# OmniMotor_MotorOnly.net
KiCad netlist of a schematic drawn in EAGLE
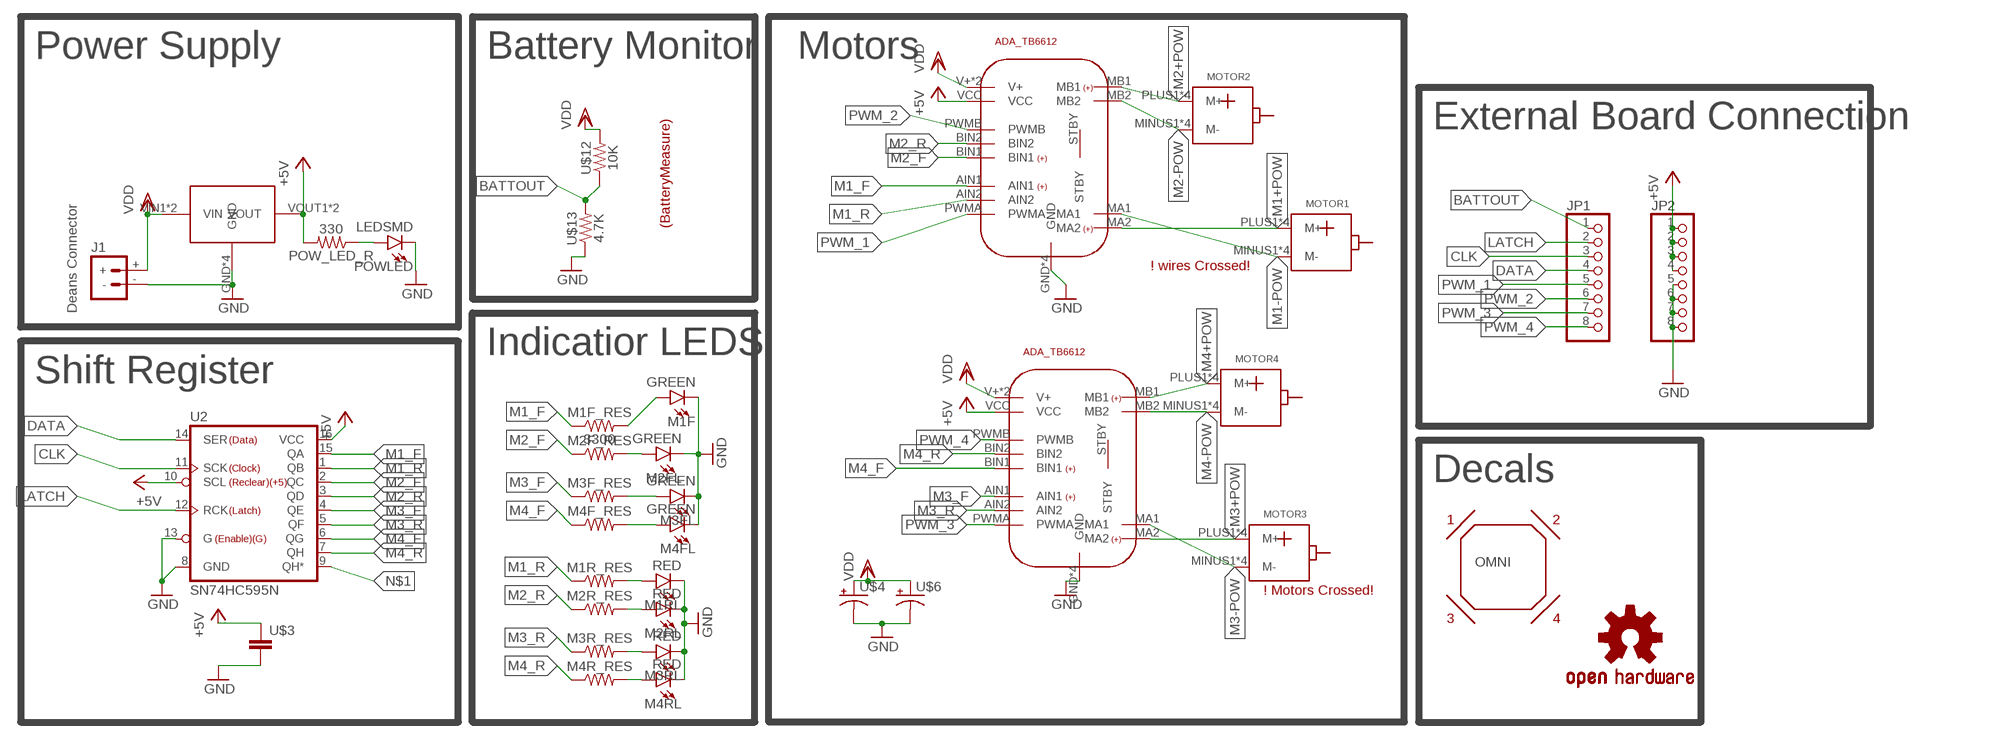
[diagram p0: schematic, sheet 1]

(export (version "E")
  (design (tool "Eeschema 10.0.6"))
  (components
    (comp (ref "J1")
      (value "BATTERY_CONN_DEANS")
      (footprint "eagle-import:DEANS")
      (libsource (lib "eagle-import") (part "BATTERY_CONN_DEANS"))
    )
    (comp (ref "JP1")
      (value "PINHD-1X8BIG")
      (footprint "eagle-import:1X08-BIG")
      (libsource (lib "eagle-import") (part "PINHD-1X8BIG"))
    )
    (comp (ref "JP2")
      (value "PINHD-1X8BIG")
      (footprint "eagle-import:1X08-BIG")
      (libsource (lib "eagle-import") (part "PINHD-1X8BIG"))
    )
    (comp (ref "LOGO1")
      (value "OSHW-LOGOL")
      (footprint "eagle-import:OSHW-LOGO-L")
      (libsource (lib "eagle-import") (part "OSHW-LOGOL"))
    )
    (comp (ref "M1F")
      (value "GREEN")
      (footprint "eagle-import:LED_SMD")
      (libsource (lib "eagle-import") (part "LEDSMD"))
    )
    (comp (ref "M1F_RES")
      (value "3300")
      (footprint "eagle-import:R1206")
      (libsource (lib "eagle-import") (part "RESISTORSMD"))
    )
    (comp (ref "M1RL")
      (value "RED")
      (footprint "eagle-import:LED_SMD")
      (libsource (lib "eagle-import") (part "LEDSMD"))
    )
    (comp (ref "M1R_RES")
      (value "RESISTORSMD")
      (footprint "eagle-import:R1206")
      (libsource (lib "eagle-import") (part "RESISTORSMD"))
    )
    (comp (ref "M2FL")
      (value "GREEN")
      (footprint "eagle-import:LED_SMD")
      (libsource (lib "eagle-import") (part "LEDSMD"))
    )
    (comp (ref "M2F_RES")
      (value "RESISTORSMD")
      (footprint "eagle-import:R1206")
      (libsource (lib "eagle-import") (part "RESISTORSMD"))
    )
    (comp (ref "M2RL")
      (value "RED")
      (footprint "eagle-import:LED_SMD")
      (libsource (lib "eagle-import") (part "LEDSMD"))
    )
    (comp (ref "M2R_RES")
      (value "RESISTORSMD")
      (footprint "eagle-import:R1206")
      (libsource (lib "eagle-import") (part "RESISTORSMD"))
    )
    (comp (ref "M3FL")
      (value "GREEN")
      (footprint "eagle-import:LED_SMD")
      (libsource (lib "eagle-import") (part "LEDSMD"))
    )
    (comp (ref "M3F_RES")
      (value "RESISTORSMD")
      (footprint "eagle-import:R1206")
      (libsource (lib "eagle-import") (part "RESISTORSMD"))
    )
    (comp (ref "M3RL")
      (value "RED")
      (footprint "eagle-import:LED_SMD")
      (libsource (lib "eagle-import") (part "LEDSMD"))
    )
    (comp (ref "M3R_RES")
      (value "RESISTORSMD")
      (footprint "eagle-import:R1206")
      (libsource (lib "eagle-import") (part "RESISTORSMD"))
    )
    (comp (ref "M4FL")
      (value "GREEN")
      (footprint "eagle-import:LED_SMD")
      (libsource (lib "eagle-import") (part "LEDSMD"))
    )
    (comp (ref "M4F_RES")
      (value "RESISTORSMD")
      (footprint "eagle-import:R1206")
      (libsource (lib "eagle-import") (part "RESISTORSMD"))
    )
    (comp (ref "M4RL")
      (value "RED")
      (footprint "eagle-import:LED_SMD")
      (libsource (lib "eagle-import") (part "LEDSMD"))
    )
    (comp (ref "M4R_RES")
      (value "RESISTORSMD")
      (footprint "eagle-import:R1206")
      (libsource (lib "eagle-import") (part "RESISTORSMD"))
    )
    (comp (ref "MOTOR1")
      (value "MOTOR_DC")
      (footprint "eagle-import:MOTOR_DC")
      (libsource (lib "eagle-import") (part "MOTOR_DC"))
    )
    (comp (ref "MOTOR2")
      (value "MOTOR_DC")
      (footprint "eagle-import:MOTOR_DC")
      (libsource (lib "eagle-import") (part "MOTOR_DC"))
    )
    (comp (ref "MOTOR3")
      (value "MOTOR_DC")
      (footprint "eagle-import:MOTOR_DC")
      (libsource (lib "eagle-import") (part "MOTOR_DC"))
    )
    (comp (ref "MOTOR4")
      (value "MOTOR_DC")
      (footprint "eagle-import:MOTOR_DC")
      (libsource (lib "eagle-import") (part "MOTOR_DC"))
    )
    (comp (ref "OMNI")
      (value "OMNI")
      (footprint "eagle-import:OMNI")
      (libsource (lib "eagle-import") (part "OMNI"))
    )
    (comp (ref "POWLED")
      (value "LEDSMD")
      (footprint "eagle-import:LED_SMD")
      (libsource (lib "eagle-import") (part "LEDSMD"))
    )
    (comp (ref "POW_LED_R")
      (value "330")
      (footprint "eagle-import:R1206")
      (libsource (lib "eagle-import") (part "RESISTORSMD"))
    )
    (comp (ref "U$1")
      (value "ADA_TB6612")
      (footprint "eagle-import:ADA_TB6612")
      (libsource (lib "eagle-import") (part "ADA_TB6612"))
    )
    (comp (ref "U$2")
      (value "ADA_TB6612")
      (footprint "eagle-import:ADA_TB6612")
      (libsource (lib "eagle-import") (part "ADA_TB6612"))
    )
    (comp (ref "U$3")
      (value "CAP_SMCAP")
      (footprint "eagle-import:C1206")
      (libsource (lib "eagle-import") (part "CAP_SMCAP"))
    )
    (comp (ref "U$4")
      (value "CAP_EMED")
      (footprint "eagle-import:CAP_E")
      (libsource (lib "eagle-import") (part "CAP_EMED"))
    )
    (comp (ref "U$5")
      (value "STEPDOWNGREEN")
      (footprint "eagle-import:STEPDOWN")
      (libsource (lib "eagle-import") (part "STEPDOWNGREEN"))
    )
    (comp (ref "U$6")
      (value "CAP_EMED")
      (footprint "eagle-import:CAP_E")
      (libsource (lib "eagle-import") (part "CAP_EMED"))
    )
    (comp (ref "U$12")
      (value "10K")
      (footprint "eagle-import:R1206")
      (libsource (lib "eagle-import") (part "RESISTORSMD"))
    )
    (comp (ref "U$13")
      (value "4.7K")
      (footprint "eagle-import:R1206")
      (libsource (lib "eagle-import") (part "RESISTORSMD"))
    )
    (comp (ref "U2")
      (value "SN74HC595N")
      (footprint "eagle-import:DIP16")
      (libsource (lib "eagle-import") (part "74595NHC"))
    )
  )
  (nets
    (net (code "1") (name "+5V") (class "Default")
      (node (ref "JP2") (pin "1") (pinfunction "1_1") (pintype "passive"))
      (node (ref "JP2") (pin "2") (pinfunction "2_2") (pintype "passive"))
      (node (ref "JP2") (pin "3") (pinfunction "3_3") (pintype "passive"))
      (node (ref "JP2") (pin "4") (pinfunction "4_4") (pintype "passive"))
      (node (ref "POW_LED_R") (pin "2") (pinfunction "2_2") (pintype "passive"))
      (node (ref "U$1") (pin "VCC") (pinfunction "VCC_VCC") (pintype "passive"))
      (node (ref "U$2") (pin "VCC") (pinfunction "VCC_VCC") (pintype "passive"))
      (node (ref "U$3") (pin "1") (pinfunction "1_1") (pintype "passive"))
      (node (ref "U$5") (pin "VOUT1") (pinfunction "VOUT_VOUT1") (pintype "passive"))
      (node (ref "U$5") (pin "VOUT2") (pinfunction "VOUT_VOUT2") (pintype "passive"))
      (node (ref "U2") (pin "10") (pinfunction "SCL_10") (pintype "input"))
      (node (ref "U2") (pin "16") (pinfunction "VCC_16") (pintype "power_in"))
    )
    (net (code "2") (name "BATTOUT") (class "Default")
      (node (ref "JP1") (pin "1") (pinfunction "1_1") (pintype "passive"))
      (node (ref "U$12") (pin "1") (pinfunction "1_1") (pintype "passive"))
      (node (ref "U$13") (pin "2") (pinfunction "2_2") (pintype "passive"))
    )
    (net (code "3") (name "CLK") (class "Default")
      (node (ref "JP1") (pin "3") (pinfunction "3_3") (pintype "passive"))
      (node (ref "U2") (pin "11") (pinfunction "SCK_11") (pintype "input"))
    )
    (net (code "4") (name "DATA") (class "Default")
      (node (ref "JP1") (pin "4") (pinfunction "4_4") (pintype "passive"))
      (node (ref "U2") (pin "14") (pinfunction "SER_14") (pintype "input"))
    )
    (net (code "5") (name "GND") (class "Default")
      (node (ref "J1") (pin "-") (pinfunction "-_-") (pintype "passive"))
      (node (ref "JP2") (pin "5") (pinfunction "5_5") (pintype "passive"))
      (node (ref "JP2") (pin "6") (pinfunction "6_6") (pintype "passive"))
      (node (ref "JP2") (pin "7") (pinfunction "7_7") (pintype "passive"))
      (node (ref "JP2") (pin "8") (pinfunction "8_8") (pintype "passive"))
      (node (ref "M1F") (pin "C") (pinfunction "C_C") (pintype "passive"))
      (node (ref "M1RL") (pin "C") (pinfunction "C_C") (pintype "passive"))
      (node (ref "M2FL") (pin "C") (pinfunction "C_C") (pintype "passive"))
      (node (ref "M2RL") (pin "C") (pinfunction "C_C") (pintype "passive"))
      (node (ref "M3FL") (pin "C") (pinfunction "C_C") (pintype "passive"))
      (node (ref "M3RL") (pin "C") (pinfunction "C_C") (pintype "passive"))
      (node (ref "M4FL") (pin "C") (pinfunction "C_C") (pintype "passive"))
      (node (ref "M4RL") (pin "C") (pinfunction "C_C") (pintype "passive"))
      (node (ref "POWLED") (pin "C") (pinfunction "C_C") (pintype "passive"))
      (node (ref "U$1") (pin "GND") (pinfunction "GND_GND") (pintype "passive"))
      (node (ref "U$1") (pin "GND2") (pinfunction "GND_GND2") (pintype "passive"))
      (node (ref "U$1") (pin "GND3") (pinfunction "GND_GND3") (pintype "passive"))
      (node (ref "U$1") (pin "GND4") (pinfunction "GND_GND4") (pintype "passive"))
      (node (ref "U$13") (pin "1") (pinfunction "1_1") (pintype "passive"))
      (node (ref "U$2") (pin "GND") (pinfunction "GND_GND") (pintype "passive"))
      (node (ref "U$2") (pin "GND2") (pinfunction "GND_GND2") (pintype "passive"))
      (node (ref "U$2") (pin "GND3") (pinfunction "GND_GND3") (pintype "passive"))
      (node (ref "U$2") (pin "GND4") (pinfunction "GND_GND4") (pintype "passive"))
      (node (ref "U$3") (pin "2") (pinfunction "2_2") (pintype "passive"))
      (node (ref "U$4") (pin "-") (pinfunction "-_-") (pintype "passive"))
      (node (ref "U$5") (pin "GND") (pinfunction "GND_GND") (pintype "passive"))
      (node (ref "U$5") (pin "GND2") (pinfunction "GND_GND2") (pintype "passive"))
      (node (ref "U$5") (pin "GND3") (pinfunction "GND_GND3") (pintype "passive"))
      (node (ref "U$5") (pin "GND4") (pinfunction "GND_GND4") (pintype "passive"))
      (node (ref "U$6") (pin "-") (pinfunction "-_-") (pintype "passive"))
      (node (ref "U2") (pin "13") (pinfunction "G_13") (pintype "input"))
      (node (ref "U2") (pin "8") (pinfunction "GND_8") (pintype "power_in"))
    )
    (net (code "6") (name "LATCH") (class "Default")
      (node (ref "JP1") (pin "2") (pinfunction "2_2") (pintype "passive"))
      (node (ref "U2") (pin "12") (pinfunction "RCK_12") (pintype "input"))
    )
    (net (code "7") (name "M1+POW") (class "Default")
      (node (ref "MOTOR1") (pin "PLUS1") (pinfunction "M+_PLUS1") (pintype "passive"))
      (node (ref "MOTOR1") (pin "PLUS2") (pinfunction "M+_PLUS2") (pintype "passive"))
      (node (ref "MOTOR1") (pin "PLUS3") (pinfunction "M+_PLUS3") (pintype "passive"))
      (node (ref "MOTOR1") (pin "PLUS4") (pinfunction "M+_PLUS4") (pintype "passive"))
      (node (ref "U$1") (pin "MA2") (pinfunction "MA2_MA2") (pintype "passive"))
    )
    (net (code "8") (name "M1-POW") (class "Default")
      (node (ref "MOTOR1") (pin "MINUS1") (pinfunction "M-_MINUS1") (pintype "passive"))
      (node (ref "MOTOR1") (pin "MINUS2") (pinfunction "M-_MINUS2") (pintype "passive"))
      (node (ref "MOTOR1") (pin "MINUS3") (pinfunction "M-_MINUS3") (pintype "passive"))
      (node (ref "MOTOR1") (pin "MINUS4") (pinfunction "M-_MINUS4") (pintype "passive"))
      (node (ref "U$1") (pin "MA1") (pinfunction "MA1_MA1") (pintype "passive"))
    )
    (net (code "9") (name "M1_F") (class "Default")
      (node (ref "M1F_RES") (pin "1") (pinfunction "1_1") (pintype "passive"))
      (node (ref "U$1") (pin "AIN1") (pinfunction "AIN1_AIN1") (pintype "passive"))
      (node (ref "U2") (pin "15") (pinfunction "QA_15") (pintype "tri_state"))
    )
    (net (code "10") (name "M1_R") (class "Default")
      (node (ref "M1R_RES") (pin "1") (pinfunction "1_1") (pintype "passive"))
      (node (ref "U$1") (pin "AIN2") (pinfunction "AIN2_AIN2") (pintype "passive"))
      (node (ref "U2") (pin "1") (pinfunction "QB_1") (pintype "tri_state"))
    )
    (net (code "11") (name "M2+POW") (class "Default")
      (node (ref "MOTOR2") (pin "PLUS1") (pinfunction "M+_PLUS1") (pintype "passive"))
      (node (ref "MOTOR2") (pin "PLUS2") (pinfunction "M+_PLUS2") (pintype "passive"))
      (node (ref "MOTOR2") (pin "PLUS3") (pinfunction "M+_PLUS3") (pintype "passive"))
      (node (ref "MOTOR2") (pin "PLUS4") (pinfunction "M+_PLUS4") (pintype "passive"))
      (node (ref "U$1") (pin "MB1") (pinfunction "MB1_MB1") (pintype "passive"))
    )
    (net (code "12") (name "M2-POW") (class "Default")
      (node (ref "MOTOR2") (pin "MINUS1") (pinfunction "M-_MINUS1") (pintype "passive"))
      (node (ref "MOTOR2") (pin "MINUS2") (pinfunction "M-_MINUS2") (pintype "passive"))
      (node (ref "MOTOR2") (pin "MINUS3") (pinfunction "M-_MINUS3") (pintype "passive"))
      (node (ref "MOTOR2") (pin "MINUS4") (pinfunction "M-_MINUS4") (pintype "passive"))
      (node (ref "U$1") (pin "MB2") (pinfunction "MB2_MB2") (pintype "passive"))
    )
    (net (code "13") (name "M2_F") (class "Default")
      (node (ref "M2F_RES") (pin "1") (pinfunction "1_1") (pintype "passive"))
      (node (ref "U$1") (pin "BIN1") (pinfunction "BIN1_BIN1") (pintype "passive"))
      (node (ref "U2") (pin "2") (pinfunction "QC_2") (pintype "tri_state"))
    )
    (net (code "14") (name "M2_R") (class "Default")
      (node (ref "M2R_RES") (pin "1") (pinfunction "1_1") (pintype "passive"))
      (node (ref "U$1") (pin "BIN2") (pinfunction "BIN2_BIN2") (pintype "passive"))
      (node (ref "U2") (pin "3") (pinfunction "QD_3") (pintype "tri_state"))
    )
    (net (code "15") (name "M3+POW") (class "Default")
      (node (ref "MOTOR3") (pin "PLUS1") (pinfunction "M+_PLUS1") (pintype "passive"))
      (node (ref "MOTOR3") (pin "PLUS2") (pinfunction "M+_PLUS2") (pintype "passive"))
      (node (ref "MOTOR3") (pin "PLUS3") (pinfunction "M+_PLUS3") (pintype "passive"))
      (node (ref "MOTOR3") (pin "PLUS4") (pinfunction "M+_PLUS4") (pintype "passive"))
      (node (ref "U$2") (pin "MA2") (pinfunction "MA2_MA2") (pintype "passive"))
    )
    (net (code "16") (name "M3-POW") (class "Default")
      (node (ref "MOTOR3") (pin "MINUS1") (pinfunction "M-_MINUS1") (pintype "passive"))
      (node (ref "MOTOR3") (pin "MINUS2") (pinfunction "M-_MINUS2") (pintype "passive"))
      (node (ref "MOTOR3") (pin "MINUS3") (pinfunction "M-_MINUS3") (pintype "passive"))
      (node (ref "MOTOR3") (pin "MINUS4") (pinfunction "M-_MINUS4") (pintype "passive"))
      (node (ref "U$2") (pin "MA1") (pinfunction "MA1_MA1") (pintype "passive"))
    )
    (net (code "17") (name "M3_F") (class "Default")
      (node (ref "M3F_RES") (pin "1") (pinfunction "1_1") (pintype "passive"))
      (node (ref "U$2") (pin "AIN1") (pinfunction "AIN1_AIN1") (pintype "passive"))
      (node (ref "U2") (pin "4") (pinfunction "QE_4") (pintype "tri_state"))
    )
    (net (code "18") (name "M3_R") (class "Default")
      (node (ref "M3R_RES") (pin "1") (pinfunction "1_1") (pintype "passive"))
      (node (ref "U$2") (pin "AIN2") (pinfunction "AIN2_AIN2") (pintype "passive"))
      (node (ref "U2") (pin "5") (pinfunction "QF_5") (pintype "tri_state"))
    )
    (net (code "19") (name "M4+POW") (class "Default")
      (node (ref "MOTOR4") (pin "PLUS1") (pinfunction "M+_PLUS1") (pintype "passive"))
      (node (ref "MOTOR4") (pin "PLUS2") (pinfunction "M+_PLUS2") (pintype "passive"))
      (node (ref "MOTOR4") (pin "PLUS3") (pinfunction "M+_PLUS3") (pintype "passive"))
      (node (ref "MOTOR4") (pin "PLUS4") (pinfunction "M+_PLUS4") (pintype "passive"))
      (node (ref "U$2") (pin "MB1") (pinfunction "MB1_MB1") (pintype "passive"))
    )
    (net (code "20") (name "M4-POW") (class "Default")
      (node (ref "MOTOR4") (pin "MINUS1") (pinfunction "M-_MINUS1") (pintype "passive"))
      (node (ref "MOTOR4") (pin "MINUS2") (pinfunction "M-_MINUS2") (pintype "passive"))
      (node (ref "MOTOR4") (pin "MINUS3") (pinfunction "M-_MINUS3") (pintype "passive"))
      (node (ref "MOTOR4") (pin "MINUS4") (pinfunction "M-_MINUS4") (pintype "passive"))
      (node (ref "U$2") (pin "MB2") (pinfunction "MB2_MB2") (pintype "passive"))
    )
    (net (code "21") (name "M4_F") (class "Default")
      (node (ref "M4F_RES") (pin "1") (pinfunction "1_1") (pintype "passive"))
      (node (ref "U$2") (pin "BIN1") (pinfunction "BIN1_BIN1") (pintype "passive"))
      (node (ref "U2") (pin "6") (pinfunction "QG_6") (pintype "tri_state"))
    )
    (net (code "22") (name "M4_R") (class "Default")
      (node (ref "M4R_RES") (pin "1") (pinfunction "1_1") (pintype "passive"))
      (node (ref "U$2") (pin "BIN2") (pinfunction "BIN2_BIN2") (pintype "passive"))
      (node (ref "U2") (pin "7") (pinfunction "QH_7") (pintype "tri_state"))
    )
    (net (code "23") (name "N$1") (class "Default")
      (node (ref "U2") (pin "9") (pinfunction "QH*_9") (pintype "tri_state"))
    )
    (net (code "24") (name "Net-(M1F-PadA)") (class "Default")
      (node (ref "M1F") (pin "A") (pinfunction "A_A") (pintype "passive"))
      (node (ref "M1F_RES") (pin "2") (pinfunction "2_2") (pintype "passive"))
    )
    (net (code "25") (name "Net-(M1RL-PadA)") (class "Default")
      (node (ref "M1RL") (pin "A") (pinfunction "A_A") (pintype "passive"))
      (node (ref "M1R_RES") (pin "2") (pinfunction "2_2") (pintype "passive"))
    )
    (net (code "26") (name "Net-(M2FL-PadA)") (class "Default")
      (node (ref "M2FL") (pin "A") (pinfunction "A_A") (pintype "passive"))
      (node (ref "M2F_RES") (pin "2") (pinfunction "2_2") (pintype "passive"))
    )
    (net (code "27") (name "Net-(M2RL-PadA)") (class "Default")
      (node (ref "M2RL") (pin "A") (pinfunction "A_A") (pintype "passive"))
      (node (ref "M2R_RES") (pin "2") (pinfunction "2_2") (pintype "passive"))
    )
    (net (code "28") (name "Net-(M3FL-PadA)") (class "Default")
      (node (ref "M3FL") (pin "A") (pinfunction "A_A") (pintype "passive"))
      (node (ref "M3F_RES") (pin "2") (pinfunction "2_2") (pintype "passive"))
    )
    (net (code "29") (name "Net-(M3RL-PadA)") (class "Default")
      (node (ref "M3RL") (pin "A") (pinfunction "A_A") (pintype "passive"))
      (node (ref "M3R_RES") (pin "2") (pinfunction "2_2") (pintype "passive"))
    )
    (net (code "30") (name "Net-(M4FL-PadA)") (class "Default")
      (node (ref "M4FL") (pin "A") (pinfunction "A_A") (pintype "passive"))
      (node (ref "M4F_RES") (pin "2") (pinfunction "2_2") (pintype "passive"))
    )
    (net (code "31") (name "Net-(M4RL-PadA)") (class "Default")
      (node (ref "M4RL") (pin "A") (pinfunction "A_A") (pintype "passive"))
      (node (ref "M4R_RES") (pin "2") (pinfunction "2_2") (pintype "passive"))
    )
    (net (code "32") (name "Net-(POWLED-PadA)") (class "Default")
      (node (ref "POWLED") (pin "A") (pinfunction "A_A") (pintype "passive"))
      (node (ref "POW_LED_R") (pin "1") (pinfunction "1_1") (pintype "passive"))
    )
    (net (code "33") (name "PWM_1") (class "Default")
      (node (ref "JP1") (pin "5") (pinfunction "5_5") (pintype "passive"))
      (node (ref "U$1") (pin "PWMA") (pinfunction "PWMA_PWMA") (pintype "passive"))
    )
    (net (code "34") (name "PWM_2") (class "Default")
      (node (ref "JP1") (pin "6") (pinfunction "6_6") (pintype "passive"))
      (node (ref "U$1") (pin "PWMB") (pinfunction "PWMB_PWMB") (pintype "passive"))
    )
    (net (code "35") (name "PWM_3") (class "Default")
      (node (ref "JP1") (pin "7") (pinfunction "7_7") (pintype "passive"))
      (node (ref "U$2") (pin "PWMA") (pinfunction "PWMA_PWMA") (pintype "passive"))
    )
    (net (code "36") (name "PWM_4") (class "Default")
      (node (ref "JP1") (pin "8") (pinfunction "8_8") (pintype "passive"))
      (node (ref "U$2") (pin "PWMB") (pinfunction "PWMB_PWMB") (pintype "passive"))
    )
    (net (code "37") (name "VDD") (class "Default")
      (node (ref "J1") (pin "+") (pinfunction "+_+") (pintype "passive"))
      (node (ref "U$1") (pin "V+") (pinfunction "V+_V+") (pintype "passive"))
      (node (ref "U$1") (pin "V+2") (pinfunction "V+_V+2") (pintype "passive"))
      (node (ref "U$12") (pin "2") (pinfunction "2_2") (pintype "passive"))
      (node (ref "U$2") (pin "V+") (pinfunction "V+_V+") (pintype "passive"))
      (node (ref "U$2") (pin "V+2") (pinfunction "V+_V+2") (pintype "passive"))
      (node (ref "U$4") (pin "+") (pinfunction "+_+") (pintype "passive"))
      (node (ref "U$5") (pin "VIN1") (pinfunction "VIN_VIN1") (pintype "passive"))
      (node (ref "U$5") (pin "VIN2") (pinfunction "VIN_VIN2") (pintype "passive"))
      (node (ref "U$6") (pin "+") (pinfunction "+_+") (pintype "passive"))
    )
    (net (code "38") (name "unconnected-(U$1-PadSTBY)") (class "Default")
      (node (ref "U$1") (pin "STBY") (pinfunction "STBY_STBY") (pintype "passive"))
    )
    (net (code "39") (name "unconnected-(U$2-PadSTBY)") (class "Default")
      (node (ref "U$2") (pin "STBY") (pinfunction "STBY_STBY") (pintype "passive"))
    )
  )
)
